# connectors.net
KiCad netlist of a schematic drawn in Altium Designer
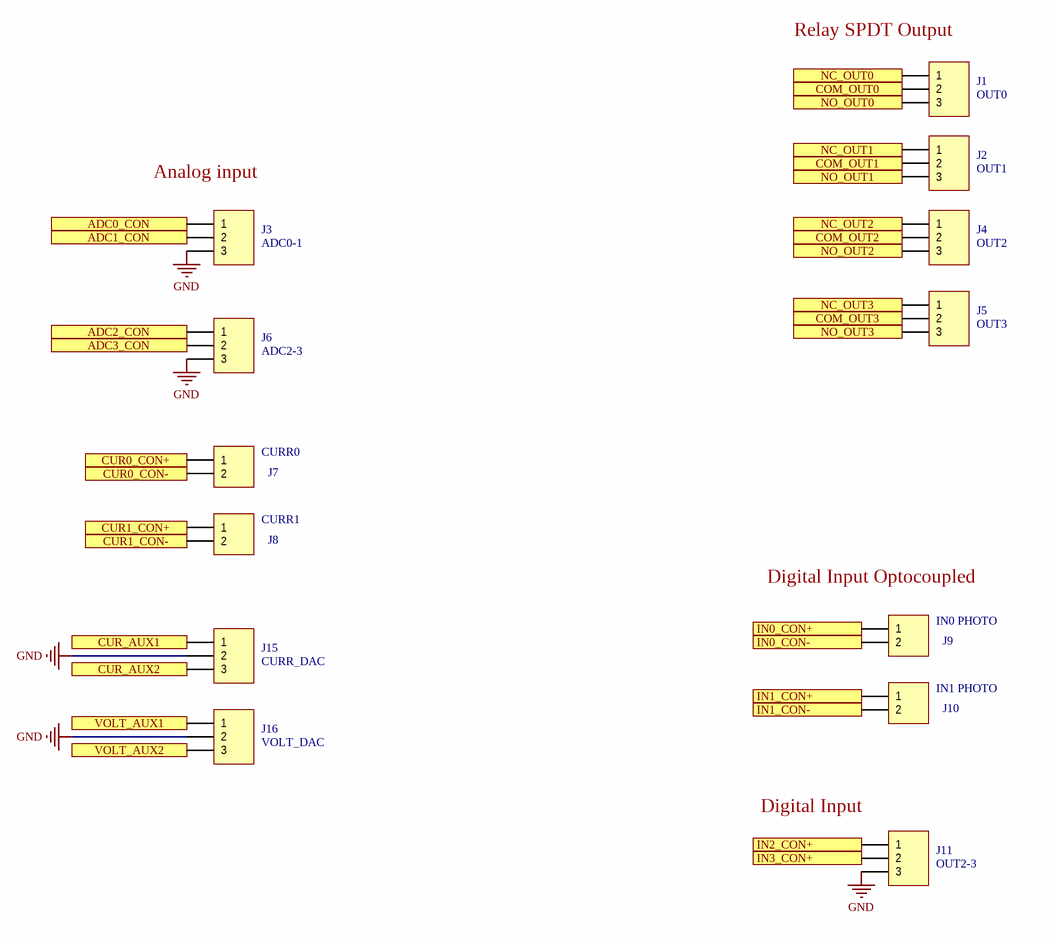
[diagram p0: connectors.SchDoc]

(export (version "E")
  (design (tool "Eeschema 10.0.6"))
  (components
    (comp (ref "J1")
      (value "OUT0")
      (footprint "TBLOCK_1X3_3.5MM_HOR_THD")
      (description "Terminal block Header 3.5mm Horizonta")
      (fields (field (name "PUBLISHER") "Altium Limited"))
      (libsource (lib "Miscellaneous Connectors") (part "Header 3"))
    )
    (comp (ref "J2")
      (value "OUT1")
      (footprint "TBLOCK_1X3_3.5MM_HOR_THD")
      (description "Terminal block Header 3.5mm Horizonta")
      (fields (field (name "PUBLISHER") "Altium Limited"))
      (libsource (lib "Miscellaneous Connectors") (part "Header 3"))
    )
    (comp (ref "J3")
      (value "ADC0-1")
      (footprint "TBLOCK_1X3_3.5MM_HOR_THD")
      (description "Terminal block Header 3.5mm Horizonta")
      (fields (field (name "PUBLISHER") "Altium Limited"))
      (libsource (lib "Miscellaneous Connectors") (part "Header 3"))
    )
    (comp (ref "J4")
      (value "OUT2")
      (footprint "TBLOCK_1X3_3.5MM_HOR_THD")
      (description "Terminal block Header 3.5mm Horizonta")
      (fields (field (name "PUBLISHER") "Altium Limited"))
      (libsource (lib "Miscellaneous Connectors") (part "Header 3"))
    )
    (comp (ref "J5")
      (value "OUT3")
      (footprint "TBLOCK_1X3_3.5MM_HOR_THD")
      (description "Terminal block Header 3.5mm Horizonta")
      (fields (field (name "PUBLISHER") "Altium Limited"))
      (libsource (lib "Miscellaneous Connectors") (part "Header 3"))
    )
    (comp (ref "J6")
      (value "ADC2-3")
      (footprint "TBLOCK_1X3_3.5MM_HOR_THD")
      (description "Terminal block Header 3.5mm Horizonta")
      (fields (field (name "PUBLISHER") "Altium Limited"))
      (libsource (lib "Miscellaneous Connectors") (part "Header 3"))
    )
    (comp (ref "J7")
      (value "CURR0")
      (footprint "TBLOCK_1X2_3.5MM_HOR_THD")
      (description "Terminal block Header 3.5mm Horizontal (WE 691322110002)")
      (fields (field (name "PUBLISHER") "Altium Limited"))
      (libsource (lib "Miscellaneous Connectors") (part "Header 2"))
    )
    (comp (ref "J8")
      (value "CURR1")
      (footprint "TBLOCK_1X2_3.5MM_HOR_THD")
      (description "Terminal block Header 3.5mm Horizontal (WE 691322110002)")
      (fields (field (name "PUBLISHER") "Altium Limited"))
      (libsource (lib "Miscellaneous Connectors") (part "Header 2"))
    )
    (comp (ref "J9")
      (value "IN0 PHOTO")
      (footprint "TBLOCK_1X2_3.5MM_HOR_THD")
      (description "Terminal block Header 3.5mm Horizontal (WE 691322110002)")
      (fields (field (name "PUBLISHER") "Altium Limited"))
      (libsource (lib "Miscellaneous Connectors") (part "Header 2"))
    )
    (comp (ref "J10")
      (value "IN1 PHOTO")
      (footprint "TBLOCK_1X2_3.5MM_HOR_THD")
      (description "Terminal block Header 3.5mm Horizontal (WE 691322110002)")
      (fields (field (name "PUBLISHER") "Altium Limited"))
      (libsource (lib "Miscellaneous Connectors") (part "Header 2"))
    )
    (comp (ref "J11")
      (value "OUT2-3")
      (footprint "TBLOCK_1X3_3.5MM_HOR_THD")
      (description "Terminal block Header 3.5mm Horizonta")
      (fields (field (name "PUBLISHER") "Altium Limited"))
      (libsource (lib "Miscellaneous Connectors") (part "Header 3"))
    )
    (comp (ref "J15")
      (value "CURR_DAC")
      (footprint "TBLOCK_1X3_3.5MM_HOR_THD")
      (description "Terminal block Header 3.5mm Horizonta")
      (fields (field (name "PUBLISHER") "Altium Limited"))
      (libsource (lib "Miscellaneous Connectors") (part "Header 3"))
    )
    (comp (ref "J16")
      (value "VOLT_DAC")
      (footprint "TBLOCK_1X3_3.5MM_HOR_THD")
      (description "Terminal block Header 3.5mm Horizonta")
      (fields (field (name "PUBLISHER") "Altium Limited"))
      (libsource (lib "Miscellaneous Connectors") (part "Header 3"))
    )
  )
  (nets
    (net (code "1") (name "/ADC0_CON") (class "Default")
      (node (ref "J3") (pin "1") (pinfunction "1_1") (pintype "passive"))
    )
    (net (code "2") (name "/ADC1_CON") (class "Default")
      (node (ref "J3") (pin "2") (pinfunction "2_2") (pintype "passive"))
    )
    (net (code "3") (name "/ADC2_CON") (class "Default")
      (node (ref "J6") (pin "1") (pinfunction "1_1") (pintype "passive"))
    )
    (net (code "4") (name "/ADC3_CON") (class "Default")
      (node (ref "J6") (pin "2") (pinfunction "2_2") (pintype "passive"))
    )
    (net (code "5") (name "/COM_OUT0") (class "Default")
      (node (ref "J1") (pin "2") (pinfunction "2_2") (pintype "passive"))
    )
    (net (code "6") (name "/COM_OUT1") (class "Default")
      (node (ref "J2") (pin "2") (pinfunction "2_2") (pintype "passive"))
    )
    (net (code "7") (name "/COM_OUT2") (class "Default")
      (node (ref "J4") (pin "2") (pinfunction "2_2") (pintype "passive"))
    )
    (net (code "8") (name "/COM_OUT3") (class "Default")
      (node (ref "J5") (pin "2") (pinfunction "2_2") (pintype "passive"))
    )
    (net (code "9") (name "/CUR0_CON+") (class "Default")
      (node (ref "J7") (pin "1") (pinfunction "1_1") (pintype "passive"))
    )
    (net (code "10") (name "/CUR0_CON-") (class "Default")
      (node (ref "J7") (pin "2") (pinfunction "2_2") (pintype "passive"))
    )
    (net (code "11") (name "/CUR1_CON+") (class "Default")
      (node (ref "J8") (pin "1") (pinfunction "1_1") (pintype "passive"))
    )
    (net (code "12") (name "/CUR1_CON-") (class "Default")
      (node (ref "J8") (pin "2") (pinfunction "2_2") (pintype "passive"))
    )
    (net (code "13") (name "/CUR_AUX1") (class "Default")
      (node (ref "J15") (pin "1") (pinfunction "1_1") (pintype "passive"))
    )
    (net (code "14") (name "/CUR_AUX2") (class "Default")
      (node (ref "J15") (pin "3") (pinfunction "3_3") (pintype "passive"))
    )
    (net (code "15") (name "/IN0_CON+") (class "Default")
      (node (ref "J9") (pin "1") (pinfunction "1_1") (pintype "passive"))
    )
    (net (code "16") (name "/IN0_CON-") (class "Default")
      (node (ref "J9") (pin "2") (pinfunction "2_2") (pintype "passive"))
    )
    (net (code "17") (name "/IN1_CON+") (class "Default")
      (node (ref "J10") (pin "1") (pinfunction "1_1") (pintype "passive"))
    )
    (net (code "18") (name "/IN1_CON-") (class "Default")
      (node (ref "J10") (pin "2") (pinfunction "2_2") (pintype "passive"))
    )
    (net (code "19") (name "/IN2_CON+") (class "Default")
      (node (ref "J11") (pin "1") (pinfunction "1_1") (pintype "passive"))
    )
    (net (code "20") (name "/IN3_CON+") (class "Default")
      (node (ref "J11") (pin "2") (pinfunction "2_2") (pintype "passive"))
    )
    (net (code "21") (name "/NC_OUT0") (class "Default")
      (node (ref "J1") (pin "1") (pinfunction "1_1") (pintype "passive"))
    )
    (net (code "22") (name "/NC_OUT1") (class "Default")
      (node (ref "J2") (pin "1") (pinfunction "1_1") (pintype "passive"))
    )
    (net (code "23") (name "/NC_OUT2") (class "Default")
      (node (ref "J4") (pin "1") (pinfunction "1_1") (pintype "passive"))
    )
    (net (code "24") (name "/NC_OUT3") (class "Default")
      (node (ref "J5") (pin "1") (pinfunction "1_1") (pintype "passive"))
    )
    (net (code "25") (name "/NO_OUT0") (class "Default")
      (node (ref "J1") (pin "3") (pinfunction "3_3") (pintype "passive"))
    )
    (net (code "26") (name "/NO_OUT1") (class "Default")
      (node (ref "J2") (pin "3") (pinfunction "3_3") (pintype "passive"))
    )
    (net (code "27") (name "/NO_OUT2") (class "Default")
      (node (ref "J4") (pin "3") (pinfunction "3_3") (pintype "passive"))
    )
    (net (code "28") (name "/NO_OUT3") (class "Default")
      (node (ref "J5") (pin "3") (pinfunction "3_3") (pintype "passive"))
    )
    (net (code "29") (name "/VOLT_AUX1") (class "Default")
      (node (ref "J16") (pin "1") (pinfunction "1_1") (pintype "passive"))
    )
    (net (code "30") (name "/VOLT_AUX2") (class "Default")
      (node (ref "J16") (pin "3") (pinfunction "3_3") (pintype "passive"))
    )
    (net (code "31") (name "GND") (class "Default")
      (node (ref "J11") (pin "3") (pinfunction "3_3") (pintype "passive"))
      (node (ref "J15") (pin "2") (pinfunction "2_2") (pintype "passive"))
      (node (ref "J16") (pin "2") (pinfunction "2_2") (pintype "passive"))
      (node (ref "J3") (pin "3") (pinfunction "3_3") (pintype "passive"))
      (node (ref "J6") (pin "3") (pinfunction "3_3") (pintype "passive"))
    )
  )
)
